# 004-floorSensor.net
KiCad netlist of a schematic drawn in EAGLE
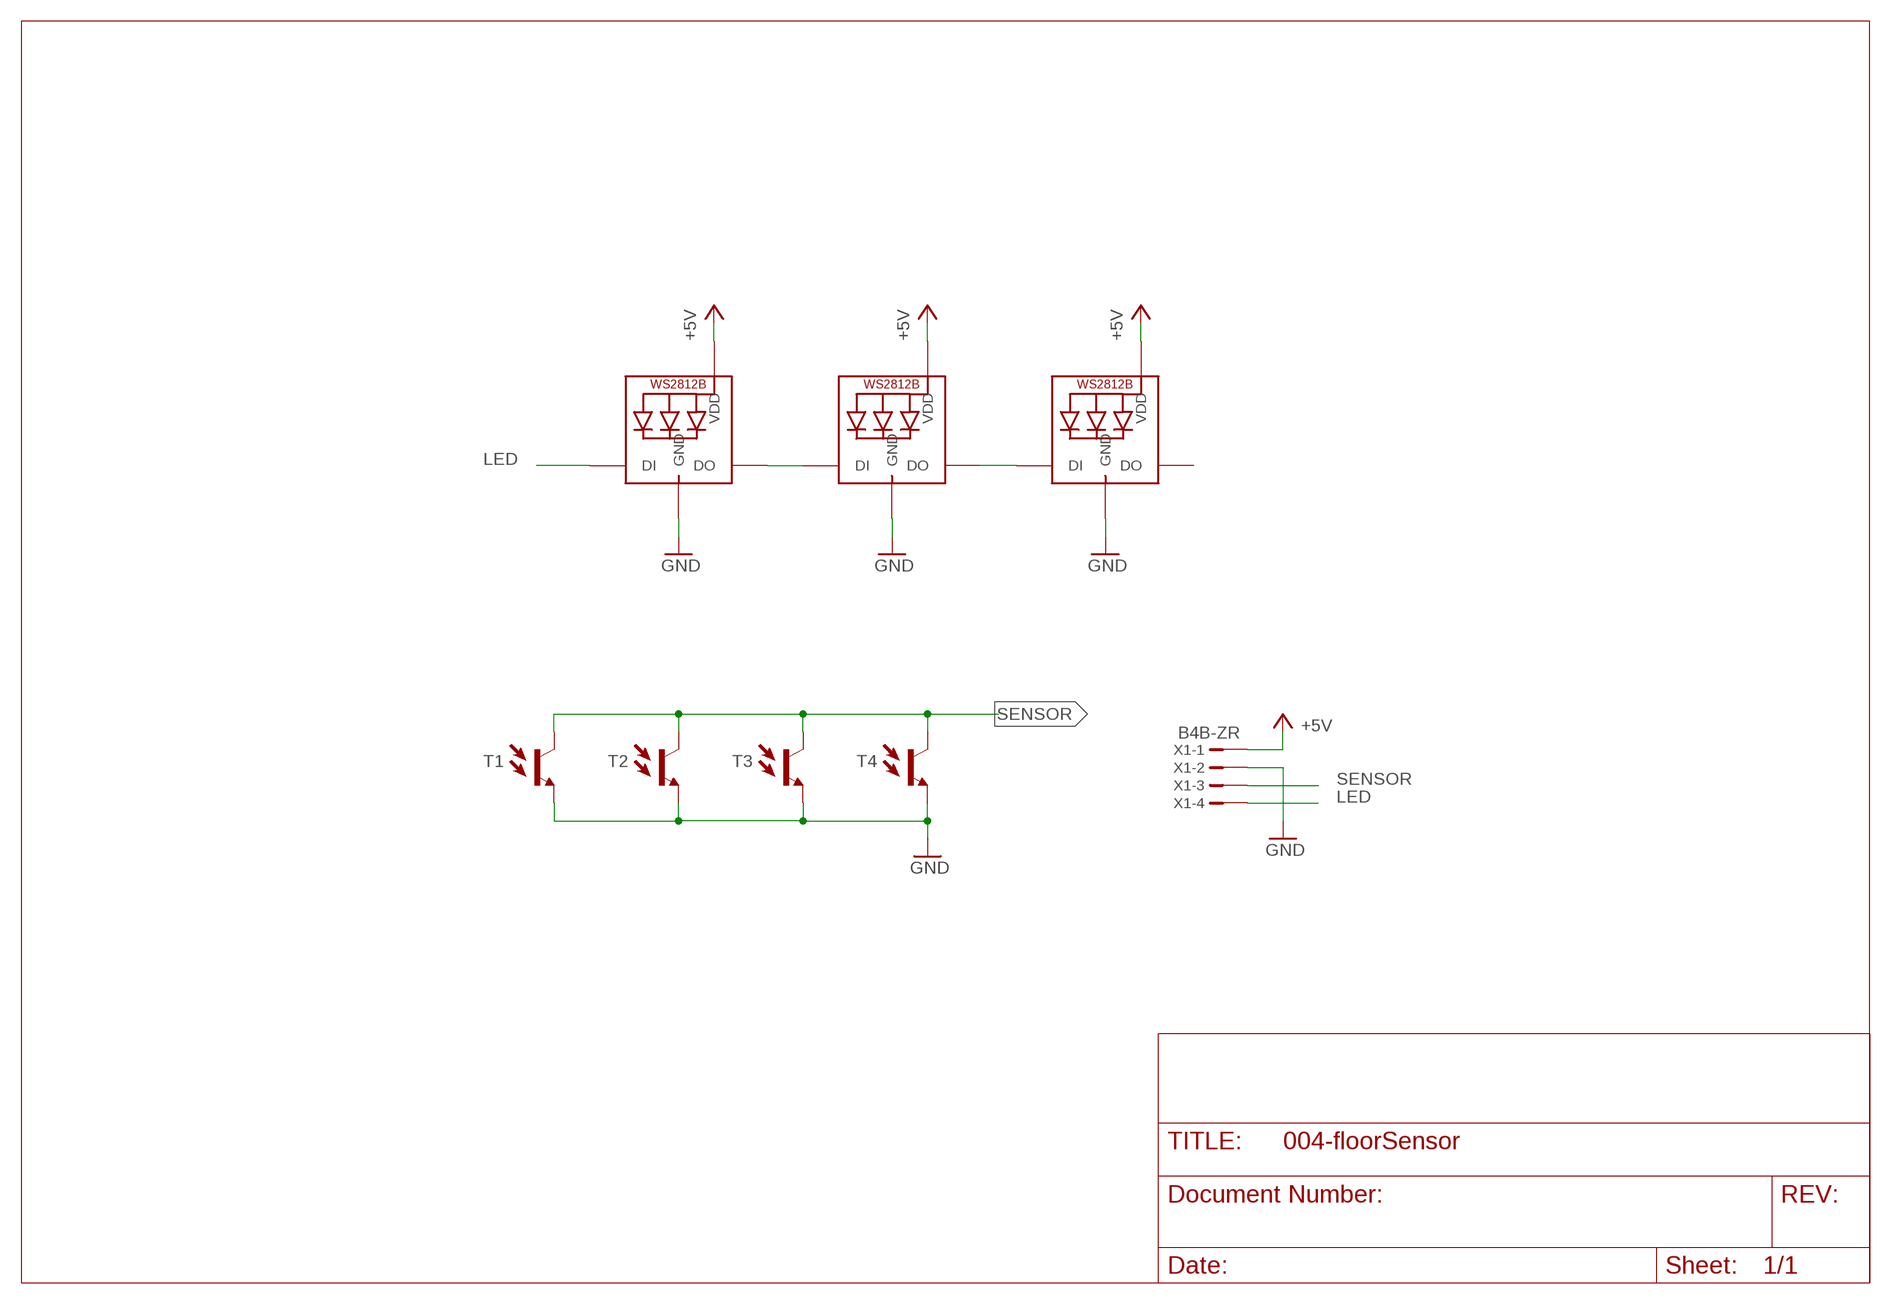
[diagram p0: schematic, sheet 1]

(export (version "E")
  (design (tool "Eeschema 10.0.6"))
  (components
    (comp (ref "LED1")
      (value "WS2812B_5050N")
      (footprint "eagle-import:WS2812B-NARROW")
      (libsource (lib "eagle-import") (part "WS2812B_5050N"))
    )
    (comp (ref "LED2")
      (value "WS2812B_5050N")
      (footprint "eagle-import:WS2812B-NARROW")
      (libsource (lib "eagle-import") (part "WS2812B_5050N"))
    )
    (comp (ref "LED3")
      (value "WS2812B_5050N")
      (footprint "eagle-import:WS2812B-NARROW")
      (libsource (lib "eagle-import") (part "WS2812B_5050N"))
    )
    (comp (ref "T1")
      (value "MYPARTS_NJL7502L")
      (footprint "eagle-import:MYPARTS_NJL7502L")
      (libsource (lib "eagle-import") (part "MYPARTS_NJL7502L"))
    )
    (comp (ref "T2")
      (value "MYPARTS_NJL7502L")
      (footprint "eagle-import:MYPARTS_NJL7502L")
      (libsource (lib "eagle-import") (part "MYPARTS_NJL7502L"))
    )
    (comp (ref "T3")
      (value "MYPARTS_NJL7502L")
      (footprint "eagle-import:MYPARTS_NJL7502L")
      (libsource (lib "eagle-import") (part "MYPARTS_NJL7502L"))
    )
    (comp (ref "T4")
      (value "MYPARTS_NJL7502L")
      (footprint "eagle-import:MYPARTS_NJL7502L")
      (libsource (lib "eagle-import") (part "MYPARTS_NJL7502L"))
    )
    (comp (ref "X1")
      (value "B4B-ZR")
      (footprint "eagle-import:B4B-ZR")
      (fields (field (name "MF") "FARNELL") (field (name "MPN") "B4B-ZR(LF)(SN)"))
      (libsource (lib "eagle-import") (part "?4B-ZRB"))
    )
  )
  (nets
    (net (code "1") (name "+5V") (class "Default")
      (node (ref "LED1") (pin "1-VDD") (pinfunction "VDD_1-VDD") (pintype "power_in"))
      (node (ref "LED2") (pin "1-VDD") (pinfunction "VDD_1-VDD") (pintype "power_in"))
      (node (ref "LED3") (pin "1-VDD") (pinfunction "VDD_1-VDD") (pintype "power_in"))
      (node (ref "X1") (pin "1") (pinfunction "1_1") (pintype "passive"))
    )
    (net (code "2") (name "/LED") (class "Default")
      (node (ref "LED1") (pin "4-DIN") (pinfunction "DI_4-DIN") (pintype "input"))
      (node (ref "X1") (pin "4") (pinfunction "1_4") (pintype "passive"))
    )
    (net (code "3") (name "GND") (class "Default")
      (node (ref "LED1") (pin "3-GND") (pinfunction "GND_3-GND") (pintype "power_in"))
      (node (ref "LED2") (pin "3-GND") (pinfunction "GND_3-GND") (pintype "power_in"))
      (node (ref "LED3") (pin "3-GND") (pinfunction "GND_3-GND") (pintype "power_in"))
      (node (ref "T1") (pin "E") (pinfunction "E_E") (pintype "passive"))
      (node (ref "T2") (pin "E") (pinfunction "E_E") (pintype "passive"))
      (node (ref "T3") (pin "E") (pinfunction "E_E") (pintype "passive"))
      (node (ref "T4") (pin "E") (pinfunction "E_E") (pintype "passive"))
      (node (ref "X1") (pin "2") (pinfunction "1_2") (pintype "passive"))
    )
    (net (code "4") (name "Net-(LED1-DO)") (class "Default")
      (node (ref "LED1") (pin "2-DOUT") (pinfunction "DO_2-DOUT") (pintype "output"))
      (node (ref "LED2") (pin "4-DIN") (pinfunction "DI_4-DIN") (pintype "input"))
    )
    (net (code "5") (name "Net-(LED2-DO)") (class "Default")
      (node (ref "LED2") (pin "2-DOUT") (pinfunction "DO_2-DOUT") (pintype "output"))
      (node (ref "LED3") (pin "4-DIN") (pinfunction "DI_4-DIN") (pintype "input"))
    )
    (net (code "6") (name "SENSOR") (class "Default")
      (node (ref "T1") (pin "C") (pinfunction "C_C") (pintype "passive"))
      (node (ref "T2") (pin "C") (pinfunction "C_C") (pintype "passive"))
      (node (ref "T3") (pin "C") (pinfunction "C_C") (pintype "passive"))
      (node (ref "T4") (pin "C") (pinfunction "C_C") (pintype "passive"))
      (node (ref "X1") (pin "3") (pinfunction "1_3") (pintype "passive"))
    )
    (net (code "7") (name "unconnected-(LED3-DO-Pad2-DOUT)") (class "Default")
      (node (ref "LED3") (pin "2-DOUT") (pinfunction "DO_2-DOUT") (pintype "output"))
    )
  )
)
